# moire_v1_3_rt.net
KiCad netlist of a schematic drawn in EAGLE
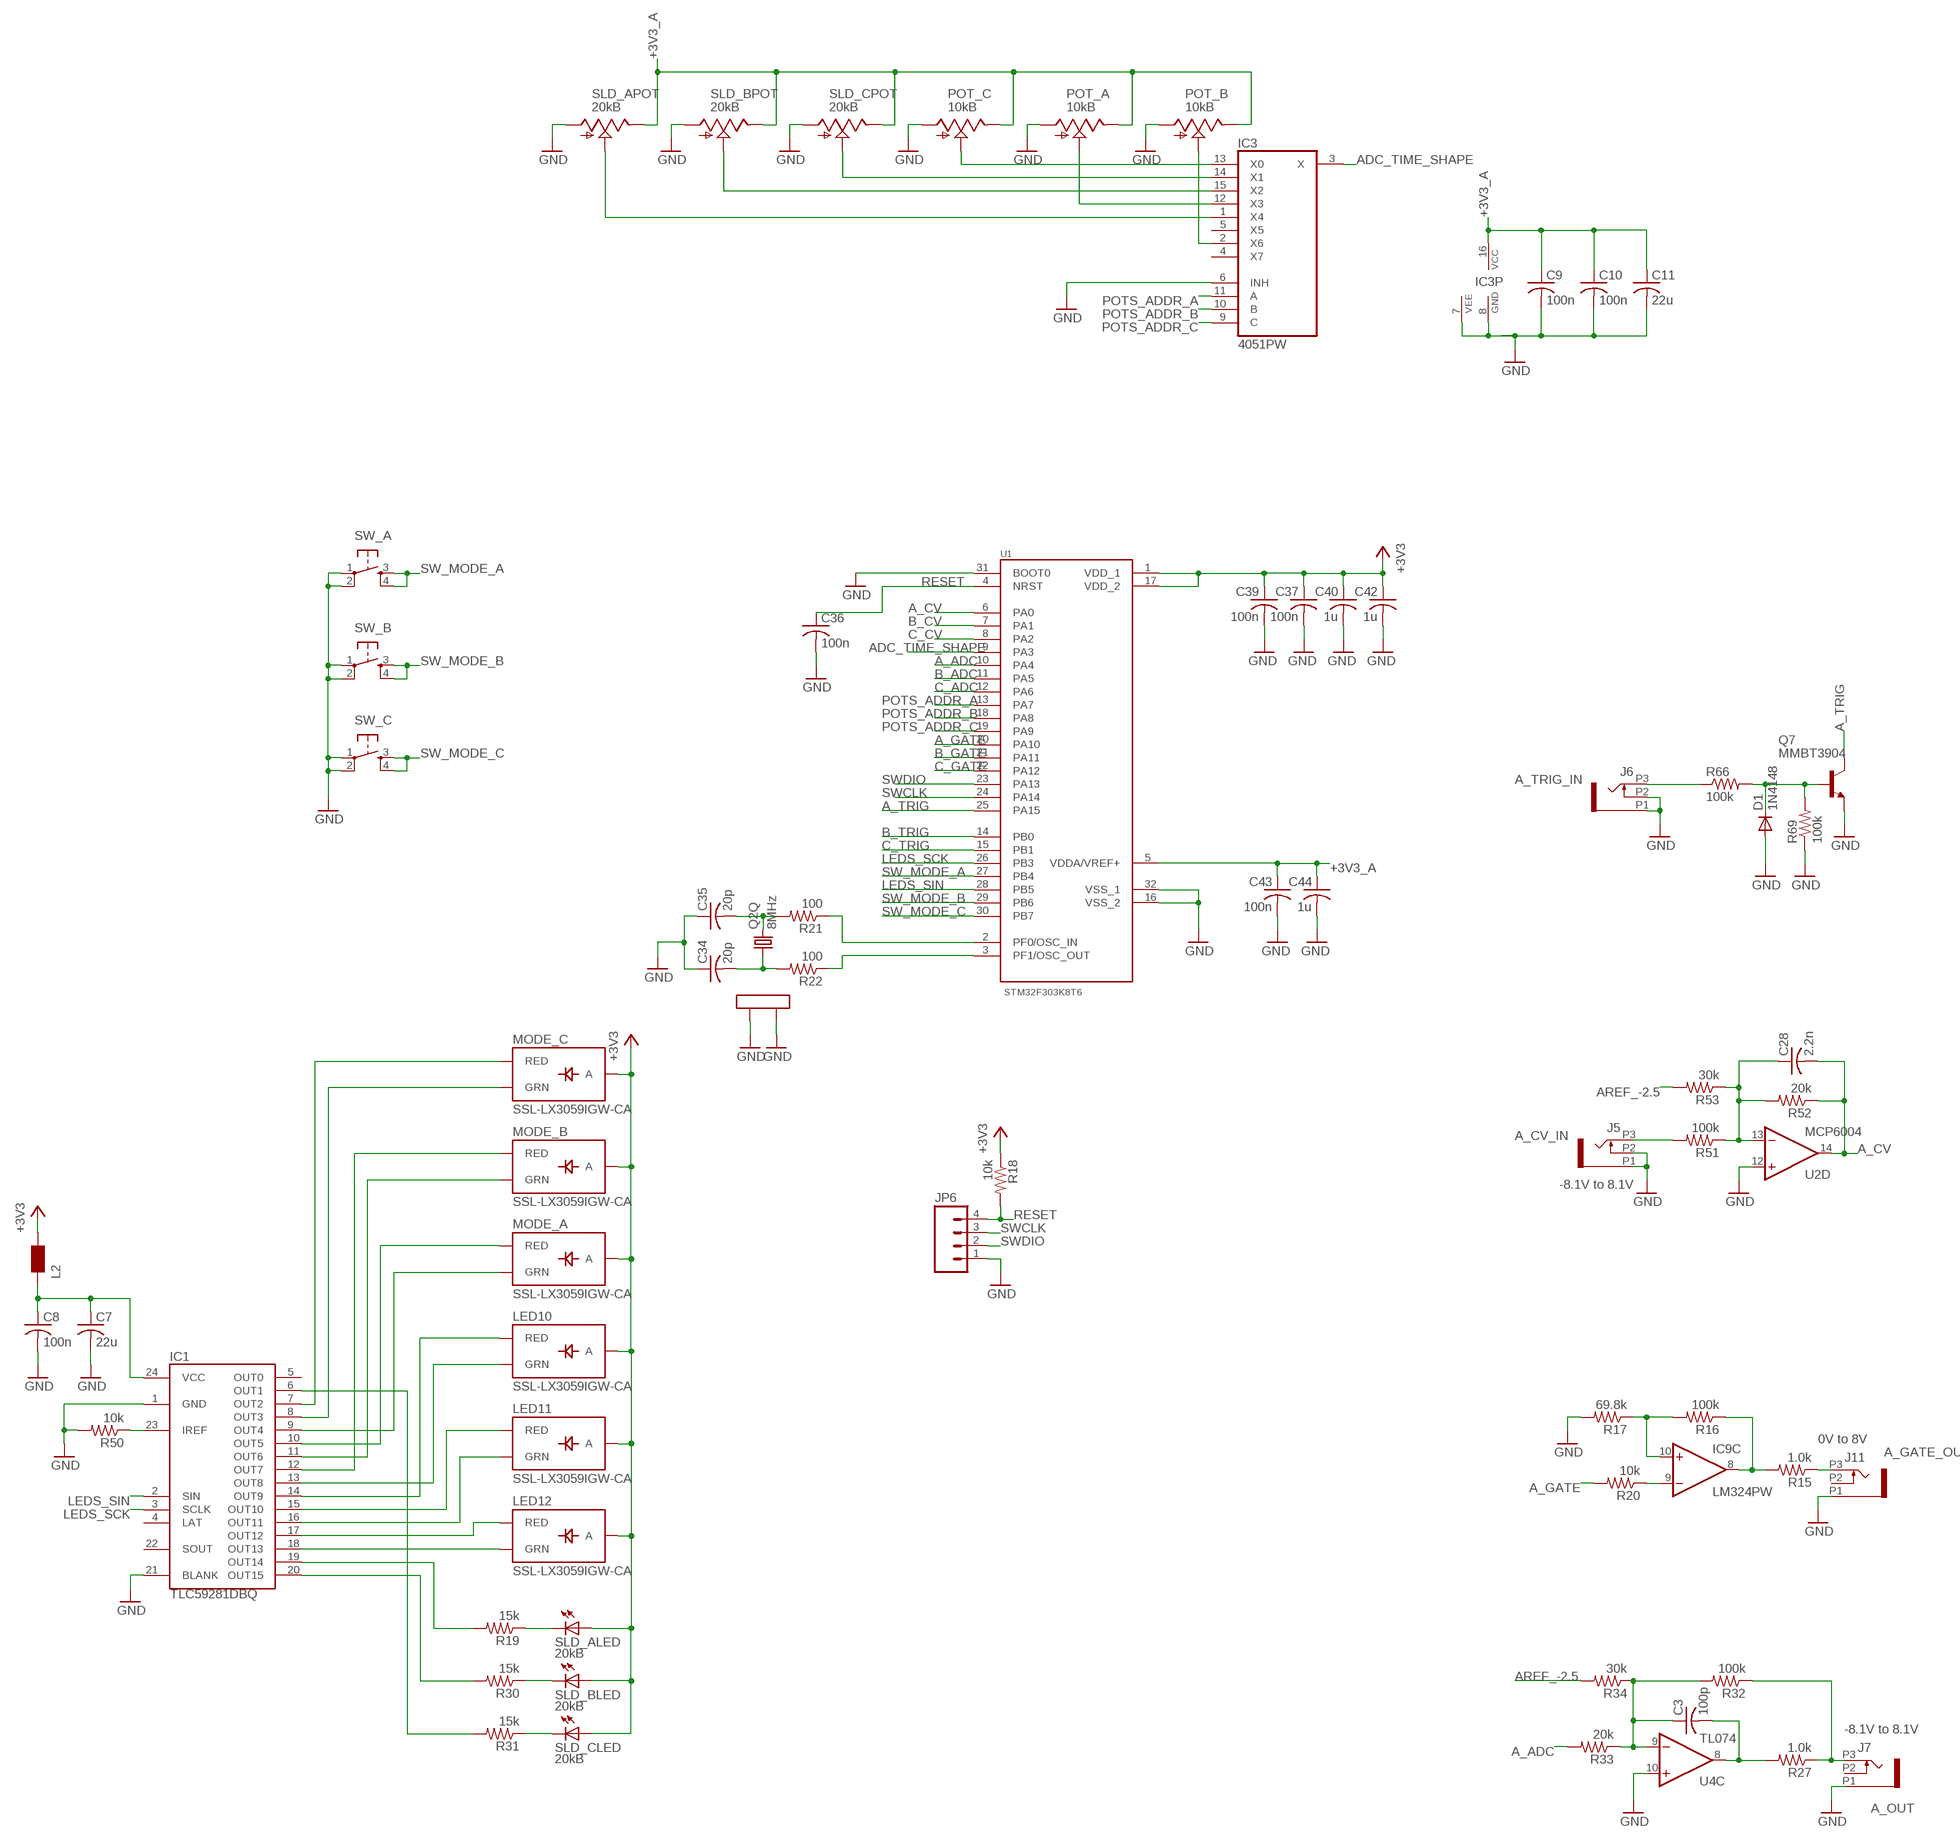
[diagram p0: schematic, sheet 1, part 1 of 2]
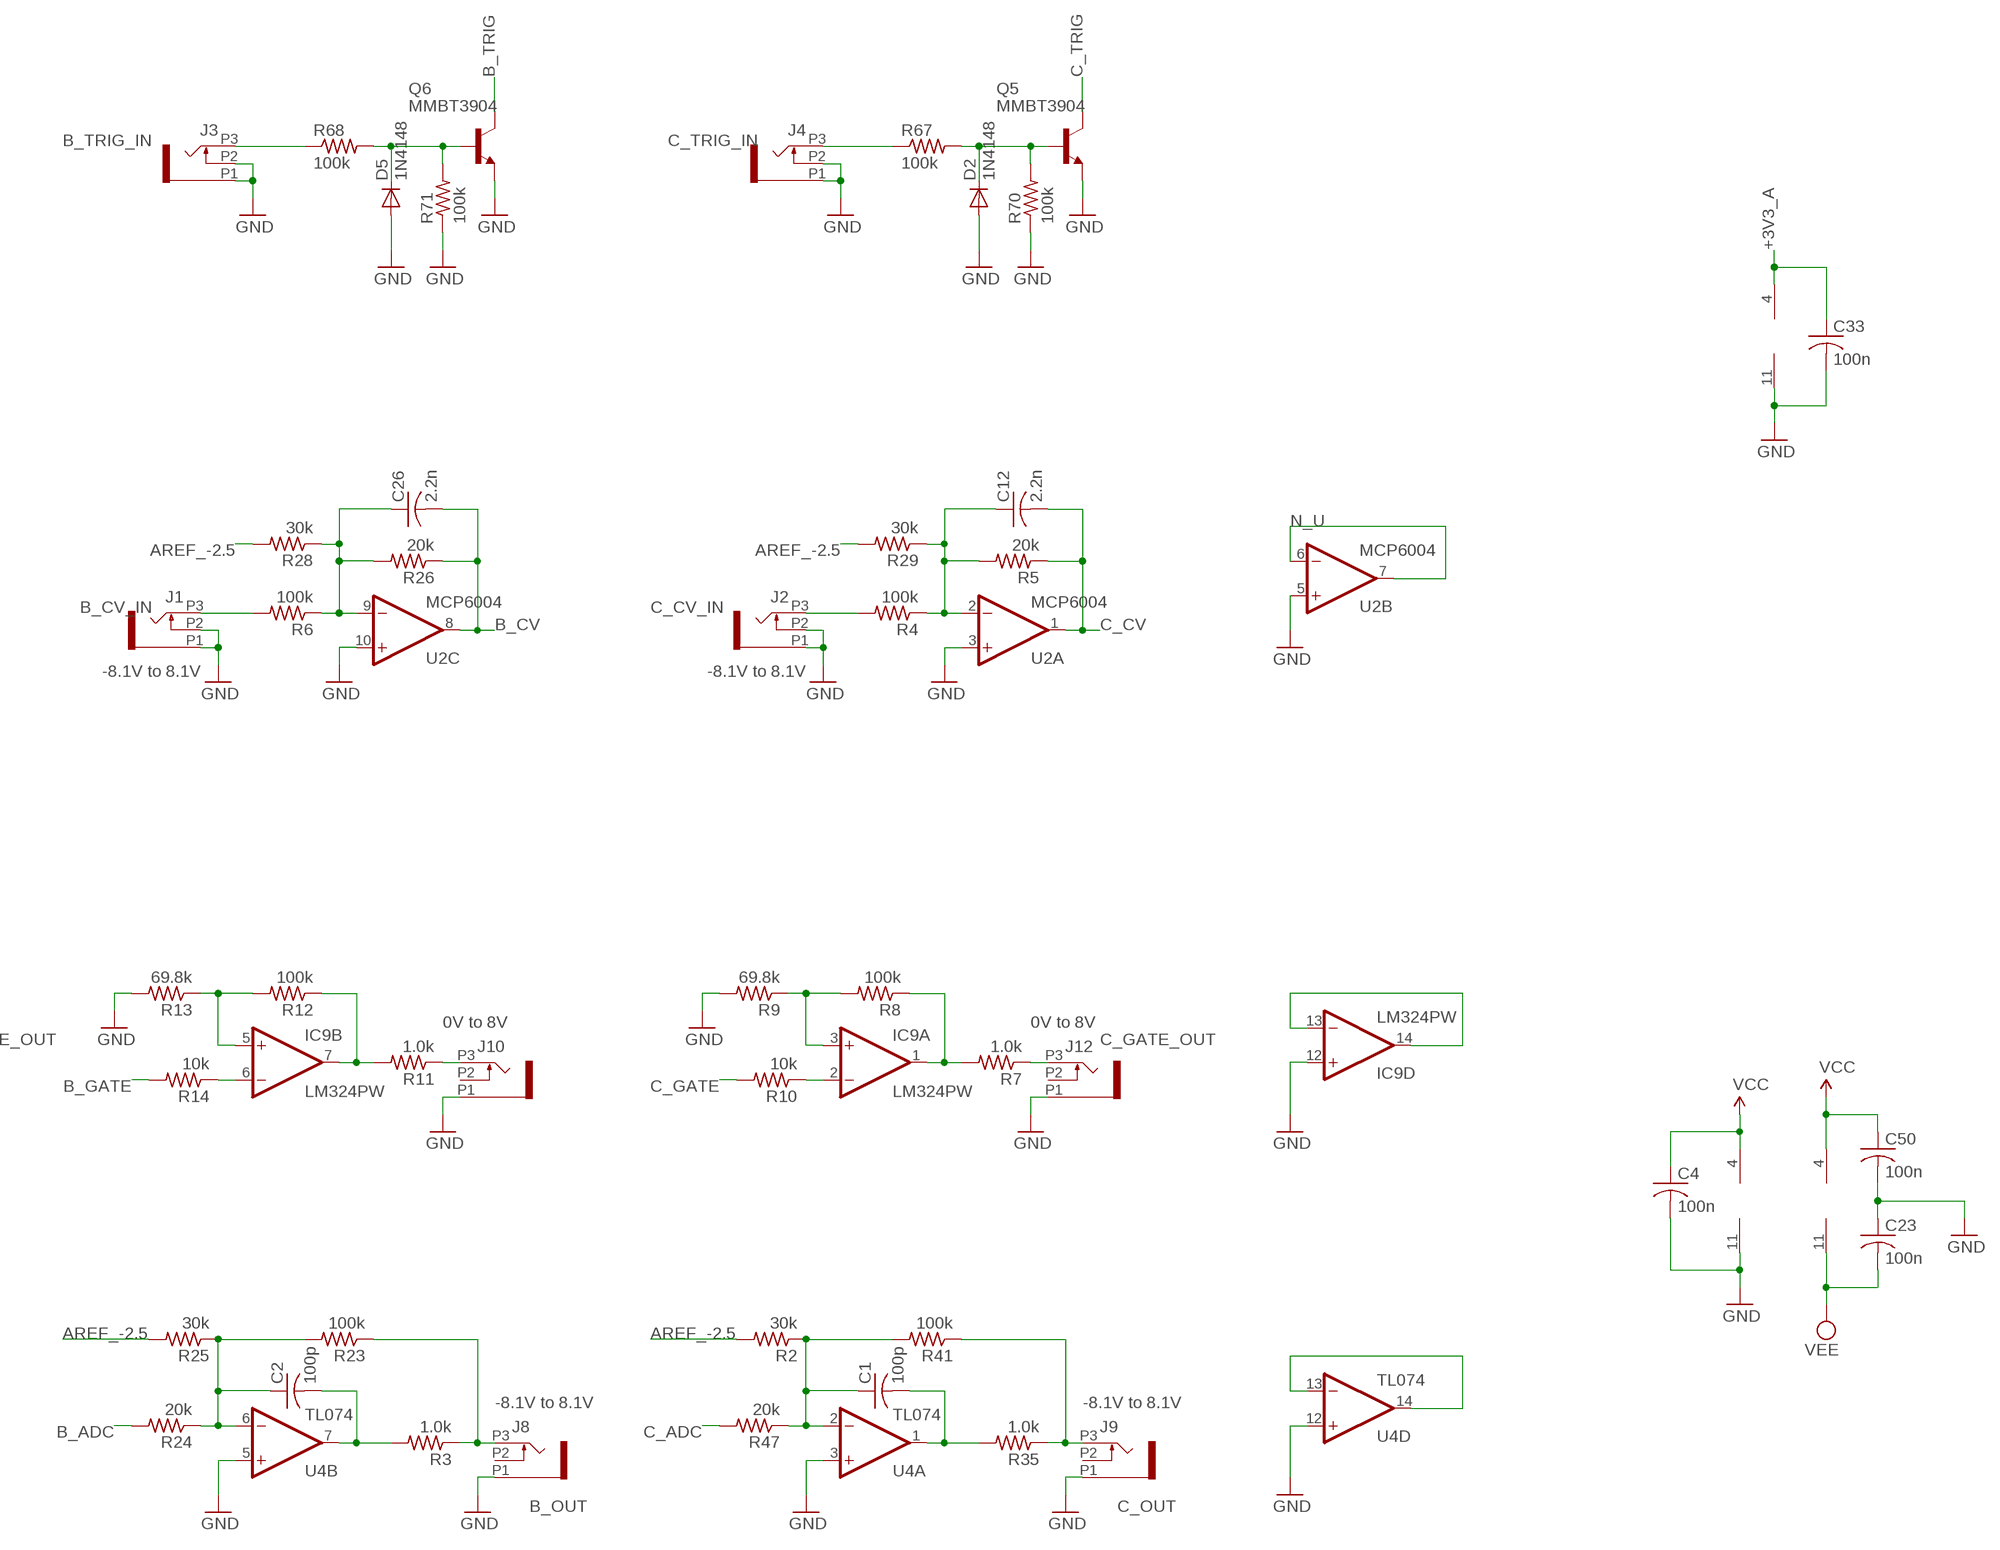
[diagram p1: schematic, sheet 1, part 2 of 2]
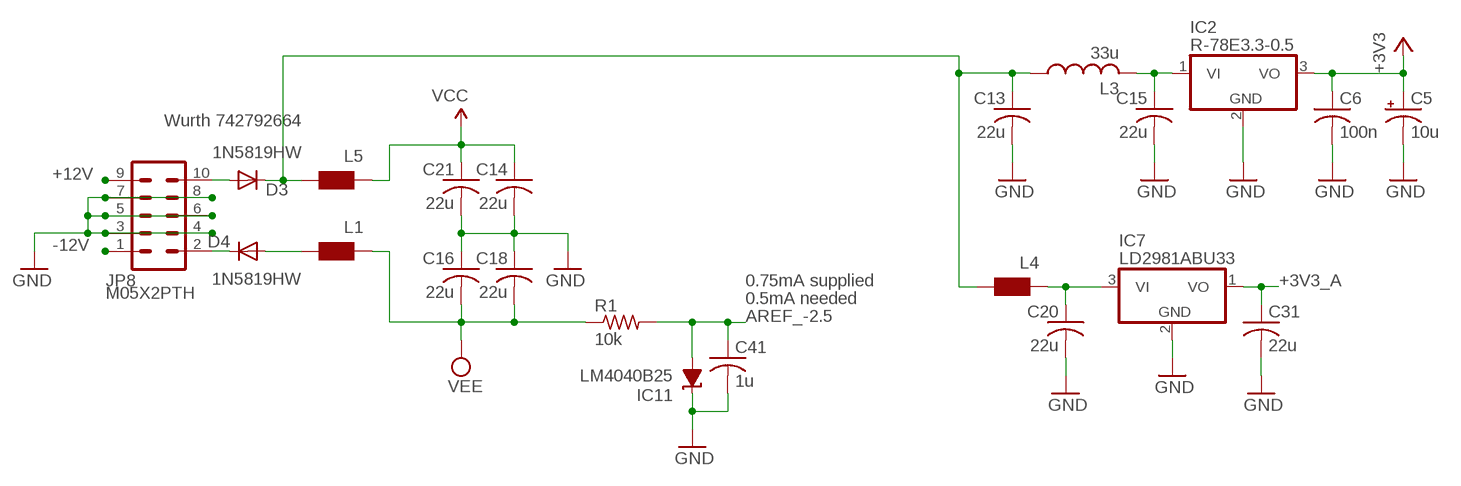
[diagram p2: schematic, sheet 2]

(export (version "E")
  (design (tool "Eeschema 10.0.6"))
  (components
    (comp (ref "C5")
      (value "10u")
      (footprint "eagle-import:PANASONIC_A")
      (libsource (lib "eagle-import") (part "CPOL-USA"))
    )
    (comp (ref "C6")
      (value "100n")
      (footprint "eagle-import:C0603")
      (libsource (lib "eagle-import") (part "C-USC0603"))
    )
    (comp (ref "C13")
      (value "22u")
      (footprint "eagle-import:C1206")
      (libsource (lib "eagle-import") (part "C-USC1206"))
    )
    (comp (ref "C14")
      (value "22u")
      (footprint "eagle-import:C1206")
      (libsource (lib "eagle-import") (part "C-USC1206"))
    )
    (comp (ref "C15")
      (value "22u")
      (footprint "eagle-import:C1206")
      (libsource (lib "eagle-import") (part "C-USC1206"))
    )
    (comp (ref "C16")
      (value "22u")
      (footprint "eagle-import:C1206")
      (libsource (lib "eagle-import") (part "C-USC1206"))
    )
    (comp (ref "C18")
      (value "22u")
      (footprint "eagle-import:C1206")
      (libsource (lib "eagle-import") (part "C-USC1206"))
    )
    (comp (ref "C20")
      (value "22u")
      (footprint "eagle-import:C1206")
      (libsource (lib "eagle-import") (part "C-USC1206"))
    )
    (comp (ref "C21")
      (value "22u")
      (footprint "eagle-import:C1206")
      (libsource (lib "eagle-import") (part "C-USC1206"))
    )
    (comp (ref "C31")
      (value "22u")
      (footprint "eagle-import:C1206")
      (libsource (lib "eagle-import") (part "C-USC1206"))
    )
    (comp (ref "C41")
      (value "1u")
      (footprint "eagle-import:C0603")
      (libsource (lib "eagle-import") (part "C-USC0603"))
    )
    (comp (ref "D3")
      (value "1N5819HW")
      (footprint "eagle-import:SOD123")
      (libsource (lib "eagle-import") (part "DIODE-SOD123"))
    )
    (comp (ref "D4")
      (value "1N5819HW")
      (footprint "eagle-import:SOD123")
      (libsource (lib "eagle-import") (part "DIODE-SOD123"))
    )
    (comp (ref "IC2")
      (value "R-78E3.3-0.5")
      (footprint "eagle-import:WE78")
      (libsource (lib "eagle-import") (part "WE173950378"))
    )
    (comp (ref "IC7")
      (value "LD2981ABU33")
      (footprint "eagle-import:SOT89")
      (libsource (lib "eagle-import") (part "LD2981ABU"))
    )
    (comp (ref "IC11")
      (value "LM4040B25")
      (footprint "eagle-import:DBZ_R-PDSO-G3")
      (libsource (lib "eagle-import") (part "LM4041DBZB12"))
    )
    (comp (ref "JP8")
      (value "M05X2PTH")
      (footprint "eagle-import:2X5-PTH")
      (libsource (lib "eagle-import") (part "M05X2PTH"))
    )
    (comp (ref "L1")
      (value "WE-CBF_0603")
      (footprint "eagle-import:0603")
      (libsource (lib "eagle-import") (part "WE-CBF_0603"))
    )
    (comp (ref "L3")
      (value "33u")
      (footprint "eagle-import:L2012C")
      (libsource (lib "eagle-import") (part "L-USL2012C"))
    )
    (comp (ref "L4")
      (value "WE-CBF_0603")
      (footprint "eagle-import:0603")
      (libsource (lib "eagle-import") (part "WE-CBF_0603"))
    )
    (comp (ref "L5")
      (value "WE-CBF_0603")
      (footprint "eagle-import:0603")
      (libsource (lib "eagle-import") (part "WE-CBF_0603"))
    )
    (comp (ref "R1")
      (value "10k")
      (footprint "eagle-import:R0603")
      (libsource (lib "eagle-import") (part "R-US_R0603"))
    )
    (comp (ref "C1")
      (value "100p")
      (footprint "eagle-import:C0603")
      (libsource (lib "eagle-import") (part "C-USC0603"))
    )
    (comp (ref "C2")
      (value "100p")
      (footprint "eagle-import:C0603")
      (libsource (lib "eagle-import") (part "C-USC0603"))
    )
    (comp (ref "C3")
      (value "100p")
      (footprint "eagle-import:C0603")
      (libsource (lib "eagle-import") (part "C-USC0603"))
    )
    (comp (ref "C4")
      (value "100n")
      (footprint "eagle-import:C0603")
      (libsource (lib "eagle-import") (part "C-USC0603"))
    )
    (comp (ref "C7")
      (value "22u")
      (footprint "eagle-import:C1206")
      (libsource (lib "eagle-import") (part "C-USC1206"))
    )
    (comp (ref "C8")
      (value "100n")
      (footprint "eagle-import:C0603")
      (libsource (lib "eagle-import") (part "C-USC0603"))
    )
    (comp (ref "C9")
      (value "100n")
      (footprint "eagle-import:C0603")
      (libsource (lib "eagle-import") (part "C-USC0603"))
    )
    (comp (ref "C10")
      (value "100n")
      (footprint "eagle-import:C0603")
      (libsource (lib "eagle-import") (part "C-USC0603"))
    )
    (comp (ref "C11")
      (value "22u")
      (footprint "eagle-import:C1206")
      (libsource (lib "eagle-import") (part "C-USC1206"))
    )
    (comp (ref "C12")
      (value "2.2n")
      (footprint "eagle-import:C0603")
      (libsource (lib "eagle-import") (part "C-USC0603"))
    )
    (comp (ref "C23")
      (value "100n")
      (footprint "eagle-import:C0603")
      (libsource (lib "eagle-import") (part "C-USC0603"))
    )
    (comp (ref "C26")
      (value "2.2n")
      (footprint "eagle-import:C0603")
      (libsource (lib "eagle-import") (part "C-USC0603"))
    )
    (comp (ref "C28")
      (value "2.2n")
      (footprint "eagle-import:C0603")
      (libsource (lib "eagle-import") (part "C-USC0603"))
    )
    (comp (ref "C33")
      (value "100n")
      (footprint "eagle-import:C0603")
      (libsource (lib "eagle-import") (part "C-USC0603"))
    )
    (comp (ref "C34")
      (value "20p")
      (footprint "eagle-import:C0603")
      (libsource (lib "eagle-import") (part "C-USC0603"))
    )
    (comp (ref "C35")
      (value "20p")
      (footprint "eagle-import:C0603")
      (libsource (lib "eagle-import") (part "C-USC0603"))
    )
    (comp (ref "C36")
      (value "100n")
      (footprint "eagle-import:C0603")
      (libsource (lib "eagle-import") (part "C-USC0603"))
    )
    (comp (ref "C37")
      (value "100n")
      (footprint "eagle-import:C0603")
      (libsource (lib "eagle-import") (part "C-USC0603"))
    )
    (comp (ref "C39")
      (value "100n")
      (footprint "eagle-import:C0603")
      (libsource (lib "eagle-import") (part "C-USC0603"))
    )
    (comp (ref "C40")
      (value "1u")
      (footprint "eagle-import:C0603")
      (libsource (lib "eagle-import") (part "C-USC0603"))
    )
    (comp (ref "C42")
      (value "1u")
      (footprint "eagle-import:C0603")
      (libsource (lib "eagle-import") (part "C-USC0603"))
    )
    (comp (ref "C43")
      (value "100n")
      (footprint "eagle-import:C0603")
      (libsource (lib "eagle-import") (part "C-USC0603"))
    )
    (comp (ref "C44")
      (value "1u")
      (footprint "eagle-import:C0603")
      (libsource (lib "eagle-import") (part "C-USC0603"))
    )
    (comp (ref "C50")
      (value "100n")
      (footprint "eagle-import:C0603")
      (libsource (lib "eagle-import") (part "C-USC0603"))
    )
    (comp (ref "D1")
      (value "1N4148")
      (footprint "eagle-import:SOD523")
      (libsource (lib "eagle-import") (part "DIODE-SOD523"))
    )
    (comp (ref "D2")
      (value "1N4148")
      (footprint "eagle-import:SOD523")
      (libsource (lib "eagle-import") (part "DIODE-SOD523"))
    )
    (comp (ref "D5")
      (value "1N4148")
      (footprint "eagle-import:SOD523")
      (libsource (lib "eagle-import") (part "DIODE-SOD523"))
    )
    (comp (ref "IC1")
      (value "TLC59281DBQ")
      (footprint "eagle-import:TSSOP24_0635")
      (libsource (lib "eagle-import") (part "TLC59281DBQ"))
    )
    (comp (ref "IC3")
      (value "4051PW")
      (footprint "eagle-import:TSSOP16_065")
      (libsource (lib "eagle-import") (part "4051PW"))
    )
    (comp (ref "IC9")
      (value "LM324PW")
      (footprint "eagle-import:TSSOP14_065")
      (libsource (lib "eagle-import") (part "TL074PW"))
    )
    (comp (ref "J1")
      (value "PJ301_THONKICONN6")
      (footprint "eagle-import:WQP_PJ_301M6")
      (libsource (lib "eagle-import") (part "PJ301_THONKICONN6"))
    )
    (comp (ref "J2")
      (value "PJ301_THONKICONN6")
      (footprint "eagle-import:WQP_PJ_301M6")
      (libsource (lib "eagle-import") (part "PJ301_THONKICONN6"))
    )
    (comp (ref "J3")
      (value "PJ301_THONKICONN6")
      (footprint "eagle-import:WQP_PJ_301M6")
      (libsource (lib "eagle-import") (part "PJ301_THONKICONN6"))
    )
    (comp (ref "J4")
      (value "PJ301_THONKICONN6")
      (footprint "eagle-import:WQP_PJ_301M6")
      (libsource (lib "eagle-import") (part "PJ301_THONKICONN6"))
    )
    (comp (ref "J5")
      (value "PJ301_THONKICONN6")
      (footprint "eagle-import:WQP_PJ_301M6")
      (libsource (lib "eagle-import") (part "PJ301_THONKICONN6"))
    )
    (comp (ref "J6")
      (value "PJ301_THONKICONN6")
      (footprint "eagle-import:WQP_PJ_301M6")
      (libsource (lib "eagle-import") (part "PJ301_THONKICONN6"))
    )
    (comp (ref "J7")
      (value "PJ301_THONKICONN6")
      (footprint "eagle-import:WQP_PJ_301M6")
      (libsource (lib "eagle-import") (part "PJ301_THONKICONN6"))
    )
    (comp (ref "J8")
      (value "PJ301_THONKICONN6")
      (footprint "eagle-import:WQP_PJ_301M6")
      (libsource (lib "eagle-import") (part "PJ301_THONKICONN6"))
    )
    (comp (ref "J9")
      (value "PJ301_THONKICONN6")
      (footprint "eagle-import:WQP_PJ_301M6")
      (libsource (lib "eagle-import") (part "PJ301_THONKICONN6"))
    )
    (comp (ref "J10")
      (value "PJ301_THONKICONN6")
      (footprint "eagle-import:WQP_PJ_301M6")
      (libsource (lib "eagle-import") (part "PJ301_THONKICONN6"))
    )
    (comp (ref "J11")
      (value "PJ301_THONKICONN6")
      (footprint "eagle-import:WQP_PJ_301M6")
      (libsource (lib "eagle-import") (part "PJ301_THONKICONN6"))
    )
    (comp (ref "J12")
      (value "PJ301_THONKICONN6")
      (footprint "eagle-import:WQP_PJ_301M6")
      (libsource (lib "eagle-import") (part "PJ301_THONKICONN6"))
    )
    (comp (ref "JP6")
      (value "M04PTH")
      (footprint "eagle-import:1X04")
      (libsource (lib "eagle-import") (part "M04PTH"))
    )
    (comp (ref "L2")
      (value "WE-CBF_0603")
      (footprint "eagle-import:0603")
      (libsource (lib "eagle-import") (part "WE-CBF_0603"))
    )
    (comp (ref "LED10")
      (value "SSL-LX3059IGW-CA")
      (footprint "eagle-import:LED-BICOLOR-THROUGHHOLE-LUMEX")
      (libsource (lib "eagle-import") (part "LED-BICOLOR-THROUGHHOLE-CA"))
    )
    (comp (ref "LED11")
      (value "SSL-LX3059IGW-CA")
      (footprint "eagle-import:LED-BICOLOR-THROUGHHOLE-LUMEX")
      (libsource (lib "eagle-import") (part "LED-BICOLOR-THROUGHHOLE-CA"))
    )
    (comp (ref "LED12")
      (value "SSL-LX3059IGW-CA")
      (footprint "eagle-import:LED-BICOLOR-THROUGHHOLE-LUMEX")
      (libsource (lib "eagle-import") (part "LED-BICOLOR-THROUGHHOLE-CA"))
    )
    (comp (ref "MODE_A")
      (value "SSL-LX3059IGW-CA")
      (footprint "eagle-import:LED-BICOLOR-THROUGHHOLE-LUMEX")
      (libsource (lib "eagle-import") (part "LED-BICOLOR-THROUGHHOLE-CA"))
    )
    (comp (ref "MODE_B")
      (value "SSL-LX3059IGW-CA")
      (footprint "eagle-import:LED-BICOLOR-THROUGHHOLE-LUMEX")
      (libsource (lib "eagle-import") (part "LED-BICOLOR-THROUGHHOLE-CA"))
    )
    (comp (ref "MODE_C")
      (value "SSL-LX3059IGW-CA")
      (footprint "eagle-import:LED-BICOLOR-THROUGHHOLE-LUMEX")
      (libsource (lib "eagle-import") (part "LED-BICOLOR-THROUGHHOLE-CA"))
    )
    (comp (ref "POT_A")
      (value "10kB")
      (footprint "eagle-import:ALPS_POT_VERTICAL")
      (libsource (lib "eagle-import") (part "POT_USVERTICAL"))
    )
    (comp (ref "POT_B")
      (value "10kB")
      (footprint "eagle-import:ALPS_POT_VERTICAL")
      (libsource (lib "eagle-import") (part "POT_USVERTICAL"))
    )
    (comp (ref "POT_C")
      (value "10kB")
      (footprint "eagle-import:ALPS_POT_VERTICAL")
      (libsource (lib "eagle-import") (part "POT_USVERTICAL"))
    )
    (comp (ref "Q2")
      (value "8MHz")
      (footprint "eagle-import:CTS406")
      (libsource (lib "eagle-import") (part "CRYSTAL"))
    )
    (comp (ref "Q5")
      (value "MMBT3904")
      (footprint "eagle-import:SOT23-BEC")
      (libsource (lib "eagle-import") (part "-NPN-SOT23-BECMMBT3904LT1"))
    )
    (comp (ref "Q6")
      (value "MMBT3904")
      (footprint "eagle-import:SOT23-BEC")
      (libsource (lib "eagle-import") (part "-NPN-SOT23-BECMMBT3904LT1"))
    )
    (comp (ref "Q7")
      (value "MMBT3904")
      (footprint "eagle-import:SOT23-BEC")
      (libsource (lib "eagle-import") (part "-NPN-SOT23-BECMMBT3904LT1"))
    )
    (comp (ref "R2")
      (value "30k")
      (footprint "eagle-import:R0603")
      (libsource (lib "eagle-import") (part "R-US_R0603"))
    )
    (comp (ref "R3")
      (value "1.0k")
      (footprint "eagle-import:R0603")
      (libsource (lib "eagle-import") (part "R-US_R0603"))
    )
    (comp (ref "R4")
      (value "100k")
      (footprint "eagle-import:R0603")
      (libsource (lib "eagle-import") (part "R-US_R0603"))
    )
    (comp (ref "R5")
      (value "20k")
      (footprint "eagle-import:R0603")
      (libsource (lib "eagle-import") (part "R-US_R0603"))
    )
    (comp (ref "R6")
      (value "100k")
      (footprint "eagle-import:R0603")
      (libsource (lib "eagle-import") (part "R-US_R0603"))
    )
    (comp (ref "R7")
      (value "1.0k")
      (footprint "eagle-import:R0603")
      (libsource (lib "eagle-import") (part "R-US_R0603"))
    )
    (comp (ref "R8")
      (value "100k")
      (footprint "eagle-import:R0603")
      (libsource (lib "eagle-import") (part "R-US_R0603"))
    )
    (comp (ref "R9")
      (value "69.8k")
      (footprint "eagle-import:R0603")
      (libsource (lib "eagle-import") (part "R-US_R0603"))
    )
    (comp (ref "R10")
      (value "10k")
      (footprint "eagle-import:R0603")
      (libsource (lib "eagle-import") (part "R-US_R0603"))
    )
    (comp (ref "R11")
      (value "1.0k")
      (footprint "eagle-import:R0603")
      (libsource (lib "eagle-import") (part "R-US_R0603"))
    )
    (comp (ref "R12")
      (value "100k")
      (footprint "eagle-import:R0603")
      (libsource (lib "eagle-import") (part "R-US_R0603"))
    )
    (comp (ref "R13")
      (value "69.8k")
      (footprint "eagle-import:R0603")
      (libsource (lib "eagle-import") (part "R-US_R0603"))
    )
    (comp (ref "R14")
      (value "10k")
      (footprint "eagle-import:R0603")
      (libsource (lib "eagle-import") (part "R-US_R0603"))
    )
    (comp (ref "R15")
      (value "1.0k")
      (footprint "eagle-import:R0603")
      (libsource (lib "eagle-import") (part "R-US_R0603"))
    )
    (comp (ref "R16")
      (value "100k")
      (footprint "eagle-import:R0603")
      (libsource (lib "eagle-import") (part "R-US_R0603"))
    )
    (comp (ref "R17")
      (value "69.8k")
      (footprint "eagle-import:R0603")
      (libsource (lib "eagle-import") (part "R-US_R0603"))
    )
    (comp (ref "R18")
      (value "10k")
      (footprint "eagle-import:R0603")
      (libsource (lib "eagle-import") (part "R-US_R0603"))
    )
    (comp (ref "R19")
      (value "15k")
      (footprint "eagle-import:R0603")
      (libsource (lib "eagle-import") (part "R-US_R0603"))
    )
    (comp (ref "R20")
      (value "10k")
      (footprint "eagle-import:R0603")
      (libsource (lib "eagle-import") (part "R-US_R0603"))
    )
    (comp (ref "R21")
      (value "100")
      (footprint "eagle-import:R0603")
      (libsource (lib "eagle-import") (part "R-US_R0603"))
    )
    (comp (ref "R22")
      (value "100")
      (footprint "eagle-import:R0603")
      (libsource (lib "eagle-import") (part "R-US_R0603"))
    )
    (comp (ref "R23")
      (value "100k")
      (footprint "eagle-import:R0603")
      (libsource (lib "eagle-import") (part "R-US_R0603"))
    )
    (comp (ref "R24")
      (value "20k")
      (footprint "eagle-import:R0603")
      (libsource (lib "eagle-import") (part "R-US_R0603"))
    )
    (comp (ref "R25")
      (value "30k")
      (footprint "eagle-import:R0603")
      (libsource (lib "eagle-import") (part "R-US_R0603"))
    )
    (comp (ref "R26")
      (value "20k")
      (footprint "eagle-import:R0603")
      (libsource (lib "eagle-import") (part "R-US_R0603"))
    )
    (comp (ref "R27")
      (value "1.0k")
      (footprint "eagle-import:R0603")
      (libsource (lib "eagle-import") (part "R-US_R0603"))
    )
    (comp (ref "R28")
      (value "30k")
      (footprint "eagle-import:R0603")
      (libsource (lib "eagle-import") (part "R-US_R0603"))
    )
    (comp (ref "R29")
      (value "30k")
      (footprint "eagle-import:R0603")
      (libsource (lib "eagle-import") (part "R-US_R0603"))
    )
    (comp (ref "R30")
      (value "15k")
      (footprint "eagle-import:R0603")
      (libsource (lib "eagle-import") (part "R-US_R0603"))
    )
    (comp (ref "R31")
      (value "15k")
      (footprint "eagle-import:R0603")
      (libsource (lib "eagle-import") (part "R-US_R0603"))
    )
    (comp (ref "R32")
      (value "100k")
      (footprint "eagle-import:R0603")
      (libsource (lib "eagle-import") (part "R-US_R0603"))
    )
    (comp (ref "R33")
      (value "20k")
      (footprint "eagle-import:R0603")
      (libsource (lib "eagle-import") (part "R-US_R0603"))
    )
    (comp (ref "R34")
      (value "30k")
      (footprint "eagle-import:R0603")
      (libsource (lib "eagle-import") (part "R-US_R0603"))
    )
    (comp (ref "R35")
      (value "1.0k")
      (footprint "eagle-import:R0603")
      (libsource (lib "eagle-import") (part "R-US_R0603"))
    )
    (comp (ref "R41")
      (value "100k")
      (footprint "eagle-import:R0603")
      (libsource (lib "eagle-import") (part "R-US_R0603"))
    )
    (comp (ref "R47")
      (value "20k")
      (footprint "eagle-import:R0603")
      (libsource (lib "eagle-import") (part "R-US_R0603"))
    )
    (comp (ref "R50")
      (value "10k")
      (footprint "eagle-import:R0603")
      (libsource (lib "eagle-import") (part "R-US_R0603"))
    )
    (comp (ref "R51")
      (value "100k")
      (footprint "eagle-import:R0603")
      (libsource (lib "eagle-import") (part "R-US_R0603"))
    )
    (comp (ref "R52")
      (value "20k")
      (footprint "eagle-import:R0603")
      (libsource (lib "eagle-import") (part "R-US_R0603"))
    )
    (comp (ref "R53")
      (value "30k")
      (footprint "eagle-import:R0603")
      (libsource (lib "eagle-import") (part "R-US_R0603"))
    )
    (comp (ref "R66")
      (value "100k")
      (footprint "eagle-import:R0603")
      (libsource (lib "eagle-import") (part "R-US_R0603"))
    )
    (comp (ref "R67")
      (value "100k")
      (footprint "eagle-import:R0603")
      (libsource (lib "eagle-import") (part "R-US_R0603"))
    )
    (comp (ref "R68")
      (value "100k")
      (footprint "eagle-import:R0603")
      (libsource (lib "eagle-import") (part "R-US_R0603"))
    )
    (comp (ref "R69")
      (value "100k")
      (footprint "eagle-import:R0603")
      (libsource (lib "eagle-import") (part "R-US_R0603"))
    )
    (comp (ref "R70")
      (value "100k")
      (footprint "eagle-import:R0603")
      (libsource (lib "eagle-import") (part "R-US_R0603"))
    )
    (comp (ref "R71")
      (value "100k")
      (footprint "eagle-import:R0603")
      (libsource (lib "eagle-import") (part "R-US_R0603"))
    )
    (comp (ref "SLD_A")
      (value "20kB")
      (footprint "eagle-import:BOURNS_SLIDER")
      (libsource (lib "eagle-import") (part "BOURNS_SLIDER"))
    )
    (comp (ref "SLD_B")
      (value "20kB")
      (footprint "eagle-import:BOURNS_SLIDER")
      (libsource (lib "eagle-import") (part "BOURNS_SLIDER"))
    )
    (comp (ref "SLD_C")
      (value "20kB")
      (footprint "eagle-import:BOURNS_SLIDER")
      (libsource (lib "eagle-import") (part "BOURNS_SLIDER"))
    )
    (comp (ref "SW_A")
      (value "TAC_SWITCHPTH")
      (footprint "eagle-import:TACTILE-PTH")
      (libsource (lib "eagle-import") (part "TAC_SWITCHPTH"))
    )
    (comp (ref "SW_B")
      (value "TAC_SWITCHPTH")
      (footprint "eagle-import:TACTILE-PTH")
      (libsource (lib "eagle-import") (part "TAC_SWITCHPTH"))
    )
    (comp (ref "SW_C")
      (value "TAC_SWITCHPTH")
      (footprint "eagle-import:TACTILE-PTH")
      (libsource (lib "eagle-import") (part "TAC_SWITCHPTH"))
    )
    (comp (ref "U1")
      (value "STM32F303K8T6")
      (footprint "eagle-import:QFP80P900X900X160-32N")
      (fields (field (name "MF") "STMicroelectronics"))
      (libsource (lib "eagle-import") (part "STM32F303K8T6"))
    )
    (comp (ref "U2")
      (value "MCP6004")
      (footprint "eagle-import:SO14")
      (libsource (lib "eagle-import") (part "MCP6004_SMD"))
    )
    (comp (ref "U4")
      (value "TL074")
      (footprint "eagle-import:SO14")
      (libsource (lib "eagle-import") (part "TL074_SMD"))
    )
  )
  (nets
    (net (code "1") (name "+3V3") (class "Default")
      (node (ref "C37") (pin "1") (pinfunction "1_1") (pintype "passive"))
      (node (ref "C39") (pin "1") (pinfunction "1_1") (pintype "passive"))
      (node (ref "C40") (pin "1") (pinfunction "1_1") (pintype "passive"))
      (node (ref "C42") (pin "1") (pinfunction "1_1") (pintype "passive"))
      (node (ref "C5") (pin "+") (pinfunction "+_+") (pintype "passive"))
      (node (ref "C6") (pin "1") (pinfunction "1_1") (pintype "passive"))
      (node (ref "IC2") (pin "3") (pinfunction "VO_3") (pintype "passive"))
      (node (ref "L2") (pin "2") (pinfunction "2_2") (pintype "passive"))
      (node (ref "LED10") (pin "A") (pinfunction "A_A") (pintype "bidirectional"))
      (node (ref "LED11") (pin "A") (pinfunction "A_A") (pintype "bidirectional"))
      (node (ref "LED12") (pin "A") (pinfunction "A_A") (pintype "bidirectional"))
      (node (ref "MODE_A") (pin "A") (pinfunction "A_A") (pintype "bidirectional"))
      (node (ref "MODE_B") (pin "A") (pinfunction "A_A") (pintype "bidirectional"))
      (node (ref "MODE_C") (pin "A") (pinfunction "A_A") (pintype "bidirectional"))
      (node (ref "R18") (pin "1") (pinfunction "1_1") (pintype "passive"))
      (node (ref "SLD_A") (pin "B") (pinfunction "A_B") (pintype "passive"))
      (node (ref "SLD_B") (pin "B") (pinfunction "A_B") (pintype "passive"))
      (node (ref "SLD_C") (pin "B") (pinfunction "A_B") (pintype "passive"))
      (node (ref "U1") (pin "1") (pinfunction "VDD_1_1") (pintype "power_in"))
      (node (ref "U1") (pin "17") (pinfunction "VDD_2_17") (pintype "power_in"))
    )
    (net (code "2") (name "+3V3_A") (class "Default")
      (node (ref "C10") (pin "1") (pinfunction "1_1") (pintype "passive"))
      (node (ref "C11") (pin "1") (pinfunction "1_1") (pintype "passive"))
      (node (ref "C31") (pin "1") (pinfunction "1_1") (pintype "passive"))
      (node (ref "C33") (pin "1") (pinfunction "1_1") (pintype "passive"))
      (node (ref "C43") (pin "1") (pinfunction "1_1") (pintype "passive"))
      (node (ref "C44") (pin "1") (pinfunction "1_1") (pintype "passive"))
      (node (ref "C9") (pin "1") (pinfunction "1_1") (pintype "passive"))
      (node (ref "IC3") (pin "16") (pinfunction "VCC_16") (pintype "power_in"))
      (node (ref "IC7") (pin "1") (pinfunction "VO_1") (pintype "passive"))
      (node (ref "POT_A") (pin "P$1") (pinfunction "E_P$1") (pintype "passive"))
      (node (ref "POT_B") (pin "P$1") (pinfunction "E_P$1") (pintype "passive"))
      (node (ref "POT_C") (pin "P$1") (pinfunction "E_P$1") (pintype "passive"))
      (node (ref "SLD_A") (pin "3") (pinfunction "E_3") (pintype "passive"))
      (node (ref "SLD_B") (pin "3") (pinfunction "E_3") (pintype "passive"))
      (node (ref "SLD_C") (pin "3") (pinfunction "E_3") (pintype "passive"))
      (node (ref "U1") (pin "5") (pinfunction "VDDA/VREF+_5") (pintype "power_in"))
      (node (ref "U2") (pin "4") (pinfunction "V+_4") (pintype "power_in"))
    )
    (net (code "3") (name "+12V") (class "Default")
      (node (ref "D3") (pin "A") (pinfunction "A_A") (pintype "passive"))
      (node (ref "JP8") (pin "10") (pinfunction "10_10") (pintype "passive"))
      (node (ref "JP8") (pin "9") (pinfunction "9_9") (pintype "passive"))
    )
    (net (code "4") (name "-12V") (class "Default")
      (node (ref "D4") (pin "C") (pinfunction "C_C") (pintype "passive"))
      (node (ref "JP8") (pin "1") (pinfunction "1_1") (pintype "passive"))
      (node (ref "JP8") (pin "2") (pinfunction "2_2") (pintype "passive"))
    )
    (net (code "5") (name "ADC_TIME_SHAPE") (class "Default")
      (node (ref "IC3") (pin "3") (pinfunction "X_3") (pintype "bidirectional"))
      (node (ref "U1") (pin "9") (pinfunction "PA3_9") (pintype "bidirectional"))
    )
    (net (code "6") (name "AREF_-2.5") (class "Default")
      (node (ref "C41") (pin "1") (pinfunction "1_1") (pintype "passive"))
      (node (ref "IC11") (pin "2") (pinfunction "A_2") (pintype "passive"))
      (node (ref "R1") (pin "2") (pinfunction "2_2") (pintype "passive"))
      (node (ref "R2") (pin "2") (pinfunction "2_2") (pintype "passive"))
      (node (ref "R25") (pin "2") (pinfunction "2_2") (pintype "passive"))
      (node (ref "R28") (pin "2") (pinfunction "2_2") (pintype "passive"))
      (node (ref "R29") (pin "2") (pinfunction "2_2") (pintype "passive"))
      (node (ref "R34") (pin "2") (pinfunction "2_2") (pintype "passive"))
      (node (ref "R53") (pin "2") (pinfunction "2_2") (pintype "passive"))
    )
    (net (code "7") (name "A_ADC") (class "Default")
      (node (ref "R33") (pin "2") (pinfunction "2_2") (pintype "passive"))
      (node (ref "U1") (pin "10") (pinfunction "PA4_10") (pintype "bidirectional"))
    )
    (net (code "8") (name "A_CV") (class "Default")
      (node (ref "C28") (pin "2") (pinfunction "2_2") (pintype "passive"))
      (node (ref "R52") (pin "1") (pinfunction "1_1") (pintype "passive"))
      (node (ref "U1") (pin "6") (pinfunction "PA0_6") (pintype "bidirectional"))
      (node (ref "U2") (pin "14") (pinfunction "OUT_14") (pintype "output"))
    )
    (net (code "9") (name "A_CV_IN") (class "Default")
      (node (ref "J5") (pin "P3") (pinfunction "3_P3") (pintype "passive"))
      (node (ref "R51") (pin "2") (pinfunction "2_2") (pintype "passive"))
    )
    (net (code "10") (name "A_GATE") (class "Default")
      (node (ref "R20") (pin "2") (pinfunction "2_2") (pintype "passive"))
      (node (ref "U1") (pin "20") (pinfunction "PA10_20") (pintype "bidirectional"))
    )
    (net (code "11") (name "A_GATE_OUT") (class "Default")
      (node (ref "J11") (pin "P3") (pinfunction "3_P3") (pintype "passive"))
      (node (ref "R15") (pin "1") (pinfunction "1_1") (pintype "passive"))
    )
    (net (code "12") (name "A_OUT") (class "Default")
      (node (ref "J7") (pin "P3") (pinfunction "3_P3") (pintype "passive"))
      (node (ref "R27") (pin "1") (pinfunction "1_1") (pintype "passive"))
      (node (ref "R32") (pin "1") (pinfunction "1_1") (pintype "passive"))
    )
    (net (code "13") (name "A_TRIG") (class "Default")
      (node (ref "Q7") (pin "C") (pinfunction "C_C") (pintype "passive"))
      (node (ref "U1") (pin "25") (pinfunction "PA15_25") (pintype "bidirectional"))
    )
    (net (code "14") (name "A_TRIG_IN") (class "Default")
      (node (ref "J6") (pin "P3") (pinfunction "3_P3") (pintype "passive"))
      (node (ref "R66") (pin "1") (pinfunction "1_1") (pintype "passive"))
    )
    (net (code "15") (name "B_ADC") (class "Default")
      (node (ref "R24") (pin "2") (pinfunction "2_2") (pintype "passive"))
      (node (ref "U1") (pin "11") (pinfunction "PA5_11") (pintype "bidirectional"))
    )
    (net (code "16") (name "B_CV") (class "Default")
      (node (ref "C26") (pin "2") (pinfunction "2_2") (pintype "passive"))
      (node (ref "R26") (pin "1") (pinfunction "1_1") (pintype "passive"))
      (node (ref "U1") (pin "7") (pinfunction "PA1_7") (pintype "bidirectional"))
      (node (ref "U2") (pin "8") (pinfunction "OUT_8") (pintype "output"))
    )
    (net (code "17") (name "B_CV_IN") (class "Default")
      (node (ref "J1") (pin "P3") (pinfunction "3_P3") (pintype "passive"))
      (node (ref "R6") (pin "2") (pinfunction "2_2") (pintype "passive"))
    )
    (net (code "18") (name "B_GATE") (class "Default")
      (node (ref "R14") (pin "2") (pinfunction "2_2") (pintype "passive"))
      (node (ref "U1") (pin "21") (pinfunction "PA11_21") (pintype "bidirectional"))
    )
    (net (code "19") (name "B_OUT") (class "Default")
      (node (ref "J8") (pin "P3") (pinfunction "3_P3") (pintype "passive"))
      (node (ref "R23") (pin "1") (pinfunction "1_1") (pintype "passive"))
      (node (ref "R3") (pin "1") (pinfunction "1_1") (pintype "passive"))
    )
    (net (code "20") (name "B_TRIG") (class "Default")
      (node (ref "Q6") (pin "C") (pinfunction "C_C") (pintype "passive"))
      (node (ref "U1") (pin "14") (pinfunction "PB0_14") (pintype "bidirectional"))
    )
    (net (code "21") (name "B_TRIG_IN") (class "Default")
      (node (ref "J3") (pin "P3") (pinfunction "3_P3") (pintype "passive"))
      (node (ref "R68") (pin "1") (pinfunction "1_1") (pintype "passive"))
    )
    (net (code "22") (name "C_ADC") (class "Default")
      (node (ref "R47") (pin "2") (pinfunction "2_2") (pintype "passive"))
      (node (ref "U1") (pin "12") (pinfunction "PA6_12") (pintype "bidirectional"))
    )
    (net (code "23") (name "C_CV") (class "Default")
      (node (ref "C12") (pin "2") (pinfunction "2_2") (pintype "passive"))
      (node (ref "R5") (pin "1") (pinfunction "1_1") (pintype "passive"))
      (node (ref "U1") (pin "8") (pinfunction "PA2_8") (pintype "bidirectional"))
      (node (ref "U2") (pin "1") (pinfunction "OUT_1") (pintype "output"))
    )
    (net (code "24") (name "C_CV_IN") (class "Default")
      (node (ref "J2") (pin "P3") (pinfunction "3_P3") (pintype "passive"))
      (node (ref "R4") (pin "2") (pinfunction "2_2") (pintype "passive"))
    )
    (net (code "25") (name "C_GATE") (class "Default")
      (node (ref "R10") (pin "2") (pinfunction "2_2") (pintype "passive"))
      (node (ref "U1") (pin "22") (pinfunction "PA12_22") (pintype "bidirectional"))
    )
    (net (code "26") (name "C_GATE_OUT") (class "Default")
      (node (ref "J12") (pin "P3") (pinfunction "3_P3") (pintype "passive"))
      (node (ref "R7") (pin "1") (pinfunction "1_1") (pintype "passive"))
    )
    (net (code "27") (name "C_OUT") (class "Default")
      (node (ref "J9") (pin "P3") (pinfunction "3_P3") (pintype "passive"))
      (node (ref "R35") (pin "1") (pinfunction "1_1") (pintype "passive"))
      (node (ref "R41") (pin "1") (pinfunction "1_1") (pintype "passive"))
    )
    (net (code "28") (name "C_TRIG") (class "Default")
      (node (ref "Q5") (pin "C") (pinfunction "C_C") (pintype "passive"))
      (node (ref "U1") (pin "15") (pinfunction "PB1_15") (pintype "bidirectional"))
    )
    (net (code "29") (name "C_TRIG_IN") (class "Default")
      (node (ref "J4") (pin "P3") (pinfunction "3_P3") (pintype "passive"))
      (node (ref "R67") (pin "1") (pinfunction "1_1") (pintype "passive"))
    )
    (net (code "30") (name "GND") (class "Default")
      (node (ref "C10") (pin "2") (pinfunction "2_2") (pintype "passive"))
      (node (ref "C11") (pin "2") (pinfunction "2_2") (pintype "passive"))
      (node (ref "C13") (pin "2") (pinfunction "2_2") (pintype "passive"))
      (node (ref "C14") (pin "2") (pinfunction "2_2") (pintype "passive"))
      (node (ref "C15") (pin "2") (pinfunction "2_2") (pintype "passive"))
      (node (ref "C16") (pin "1") (pinfunction "1_1") (pintype "passive"))
      (node (ref "C18") (pin "1") (pinfunction "1_1") (pintype "passive"))
      (node (ref "C20") (pin "2") (pinfunction "2_2") (pintype "passive"))
      (node (ref "C21") (pin "2") (pinfunction "2_2") (pintype "passive"))
      (node (ref "C23") (pin "1") (pinfunction "1_1") (pintype "passive"))
      (node (ref "C31") (pin "2") (pinfunction "2_2") (pintype "passive"))
      (node (ref "C33") (pin "2") (pinfunction "2_2") (pintype "passive"))
      (node (ref "C34") (pin "1") (pinfunction "1_1") (pintype "passive"))
      (node (ref "C35") (pin "1") (pinfunction "1_1") (pintype "passive"))
      (node (ref "C36") (pin "2") (pinfunction "2_2") (pintype "passive"))
      (node (ref "C37") (pin "2") (pinfunction "2_2") (pintype "passive"))
      (node (ref "C39") (pin "2") (pinfunction "2_2") (pintype "passive"))
      (node (ref "C4") (pin "2") (pinfunction "2_2") (pintype "passive"))
      (node (ref "C40") (pin "2") (pinfunction "2_2") (pintype "passive"))
      (node (ref "C41") (pin "2") (pinfunction "2_2") (pintype "passive"))
      (node (ref "C42") (pin "2") (pinfunction "2_2") (pintype "passive"))
      (node (ref "C43") (pin "2") (pinfunction "2_2") (pintype "passive"))
      (node (ref "C44") (pin "2") (pinfunction "2_2") (pintype "passive"))
      (node (ref "C5") (pin "-") (pinfunction "-_-") (pintype "passive"))
      (node (ref "C50") (pin "2") (pinfunction "2_2") (pintype "passive"))
      (node (ref "C6") (pin "2") (pinfunction "2_2") (pintype "passive"))
      (node (ref "C7") (pin "2") (pinfunction "2_2") (pintype "passive"))
      (node (ref "C8") (pin "2") (pinfunction "2_2") (pintype "passive"))
      (node (ref "C9") (pin "2") (pinfunction "2_2") (pintype "passive"))
      (node (ref "D1") (pin "A") (pinfunction "A_A") (pintype "passive"))
      (node (ref "D2") (pin "A") (pinfunction "A_A") (pintype "passive"))
      (node (ref "D5") (pin "A") (pinfunction "A_A") (pintype "passive"))
      (node (ref "IC1") (pin "1") (pinfunction "GND_1") (pintype "bidirectional"))
      (node (ref "IC1") (pin "21") (pinfunction "BLANK_21") (pintype "bidirectional"))
      (node (ref "IC11") (pin "1") (pinfunction "C_1") (pintype "passive"))
      (node (ref "IC2") (pin "2") (pinfunction "GND_2") (pintype "passive"))
      (node (ref "IC3") (pin "6") (pinfunction "INH_6") (pintype "input"))
      (node (ref "IC3") (pin "7") (pinfunction "VEE_7") (pintype "power_in"))
      (node (ref "IC3") (pin "8") (pinfunction "GND_8") (pintype "power_in"))
      (node (ref "IC7") (pin "2") (pinfunction "GND_2") (pintype "passive"))
      (node (ref "IC9") (pin "11") (pinfunction "V-_11") (pintype "power_in"))
      (node (ref "IC9") (pin "12") (pinfunction "+IN_12") (pintype "input"))
      (node (ref "J1") (pin "P1") (pinfunction "1_P1") (pintype "passive"))
      (node (ref "J1") (pin "P2") (pinfunction "2_P2") (pintype "passive"))
      (node (ref "J10") (pin "P1") (pinfunction "1_P1") (pintype "passive"))
      (node (ref "J11") (pin "P1") (pinfunction "1_P1") (pintype "passive"))
      (node (ref "J12") (pin "P1") (pinfunction "1_P1") (pintype "passive"))
      (node (ref "J2") (pin "P1") (pinfunction "1_P1") (pintype "passive"))
      (node (ref "J2") (pin "P2") (pinfunction "2_P2") (pintype "passive"))
      (node (ref "J3") (pin "P1") (pinfunction "1_P1") (pintype "passive"))
      (node (ref "J3") (pin "P2") (pinfunction "2_P2") (pintype "passive"))
      (node (ref "J4") (pin "P1") (pinfunction "1_P1") (pintype "passive"))
      (node (ref "J4") (pin "P2") (pinfunction "2_P2") (pintype "passive"))
      (node (ref "J5") (pin "P1") (pinfunction "1_P1") (pintype "passive"))
      (node (ref "J5") (pin "P2") (pinfunction "2_P2") (pintype "passive"))
      (node (ref "J6") (pin "P1") (pinfunction "1_P1") (pintype "passive"))
      (node (ref "J6") (pin "P2") (pinfunction "2_P2") (pintype "passive"))
      (node (ref "J7") (pin "P1") (pinfunction "1_P1") (pintype "passive"))
      (node (ref "J8") (pin "P1") (pinfunction "1_P1") (pintype "passive"))
      (node (ref "J9") (pin "P1") (pinfunction "1_P1") (pintype "passive"))
      (node (ref "JP6") (pin "1") (pinfunction "1_1") (pintype "passive"))
      (node (ref "JP8") (pin "3") (pinfunction "3_3") (pintype "passive"))
      (node (ref "JP8") (pin "4") (pinfunction "4_4") (pintype "passive"))
      (node (ref "JP8") (pin "5") (pinfunction "5_5") (pintype "passive"))
      (node (ref "JP8") (pin "6") (pinfunction "6_6") (pintype "passive"))
      (node (ref "JP8") (pin "7") (pinfunction "7_7") (pintype "passive"))
      (node (ref "JP8") (pin "8") (pinfunction "8_8") (pintype "passive"))
      (node (ref "POT_A") (pin "P$3") (pinfunction "A_P$3") (pintype "passive"))
      (node (ref "POT_B") (pin "P$3") (pinfunction "A_P$3") (pintype "passive"))
      (node (ref "POT_C") (pin "P$3") (pinfunction "A_P$3") (pintype "passive"))
      (node (ref "Q2") (pin "2") (pinfunction "LID1_2") (pintype "power_in"))
      (node (ref "Q2") (pin "4") (pinfunction "LID2_4") (pintype "power_in"))
      (node (ref "Q5") (pin "E") (pinfunction "E_E") (pintype "passive"))
      (node (ref "Q6") (pin "E") (pinfunction "E_E") (pintype "passive"))
      (node (ref "Q7") (pin "E") (pinfunction "E_E") (pintype "passive"))
      (node (ref "R13") (pin "2") (pinfunction "2_2") (pintype "passive"))
      (node (ref "R17") (pin "2") (pinfunction "2_2") (pintype "passive"))
      (node (ref "R50") (pin "2") (pinfunction "2_2") (pintype "passive"))
      (node (ref "R69") (pin "1") (pinfunction "1_1") (pintype "passive"))
      (node (ref "R70") (pin "1") (pinfunction "1_1") (pintype "passive"))
      (node (ref "R71") (pin "1") (pinfunction "1_1") (pintype "passive"))
      (node (ref "R9") (pin "2") (pinfunction "2_2") (pintype "passive"))
      (node (ref "SLD_A") (pin "1") (pinfunction "A_1") (pintype "passive"))
      (node (ref "SLD_B") (pin "1") (pinfunction "A_1") (pintype "passive"))
      (node (ref "SLD_C") (pin "1") (pinfunction "A_1") (pintype "passive"))
      (node (ref "SW_A") (pin "1") (pinfunction "1_1") (pintype "passive"))
      (node (ref "SW_A") (pin "2") (pinfunction "2_2") (pintype "passive"))
      (node (ref "SW_B") (pin "1") (pinfunction "1_1") (pintype "passive"))
      (node (ref "SW_B") (pin "2") (pinfunction "2_2") (pintype "passive"))
      (node (ref "SW_C") (pin "1") (pinfunction "1_1") (pintype "passive"))
      (node (ref "SW_C") (pin "2") (pinfunction "2_2") (pintype "passive"))
      (node (ref "U1") (pin "16") (pinfunction "VSS_2_16") (pintype "power_in"))
      (node (ref "U1") (pin "31") (pinfunction "BOOT0_31") (pintype "input"))
      (node (ref "U1") (pin "32") (pinfunction "VSS_1_32") (pintype "power_in"))
      (node (ref "U2") (pin "10") (pinfunction "+IN_10") (pintype "input"))
      (node (ref "U2") (pin "11") (pinfunction "V-_11") (pintype "power_in"))
      (node (ref "U2") (pin "12") (pinfunction "+IN_12") (pintype "input"))
      (node (ref "U2") (pin "3") (pinfunction "+IN_3") (pintype "input"))
      (node (ref "U2") (pin "5") (pinfunction "+IN_5") (pintype "input"))
      (node (ref "U4") (pin "10") (pinfunction "+IN_10") (pintype "input"))
      (node (ref "U4") (pin "12") (pinfunction "+IN_12") (pintype "input"))
      (node (ref "U4") (pin "3") (pinfunction "+IN_3") (pintype "input"))
      (node (ref "U4") (pin "5") (pinfunction "+IN_5") (pintype "input"))
    )
    (net (code "31") (name "LEDS_SCK") (class "Default")
      (node (ref "IC1") (pin "3") (pinfunction "SCLK_3") (pintype "bidirectional"))
      (node (ref "U1") (pin "26") (pinfunction "PB3_26") (pintype "bidirectional"))
    )
    (net (code "32") (name "LEDS_SIN") (class "Default")
      (node (ref "IC1") (pin "2") (pinfunction "SIN_2") (pintype "bidirectional"))
      (node (ref "U1") (pin "28") (pinfunction "PB5_28") (pintype "bidirectional"))
    )
    (net (code "33") (name "N_U") (class "Default")
      (node (ref "U2") (pin "6") (pinfunction "-IN_6") (pintype "input"))
      (node (ref "U2") (pin "7") (pinfunction "OUT_7") (pintype "output"))
    )
    (net (code "34") (name "Net-(C13-Pad1)") (class "Default")
      (node (ref "C13") (pin "1") (pinfunction "1_1") (pintype "passive"))
      (node (ref "D3") (pin "C") (pinfunction "C_C") (pintype "passive"))
      (node (ref "L3") (pin "1") (pinfunction "1_1") (pintype "passive"))
      (node (ref "L4") (pin "2") (pinfunction "2_2") (pintype "passive"))
      (node (ref "L5") (pin "2") (pinfunction "2_2") (pintype "passive"))
    )
    (net (code "35") (name "Net-(C34-Pad2)") (class "Default")
      (node (ref "C34") (pin "2") (pinfunction "2_2") (pintype "passive"))
      (node (ref "Q2") (pin "1") (pinfunction "1_1") (pintype "passive"))
      (node (ref "R22") (pin "2") (pinfunction "2_2") (pintype "passive"))
    )
    (net (code "36") (name "Net-(D1-PadC)") (class "Default")
      (node (ref "D1") (pin "C") (pinfunction "C_C") (pintype "passive"))
      (node (ref "Q7") (pin "B") (pinfunction "B_B") (pintype "passive"))
      (node (ref "R66") (pin "2") (pinfunction "2_2") (pintype "passive"))
      (node (ref "R69") (pin "2") (pinfunction "2_2") (pintype "passive"))
    )
    (net (code "37") (name "Net-(D2-PadC)") (class "Default")
      (node (ref "D2") (pin "C") (pinfunction "C_C") (pintype "passive"))
      (node (ref "Q5") (pin "B") (pinfunction "B_B") (pintype "passive"))
      (node (ref "R67") (pin "2") (pinfunction "2_2") (pintype "passive"))
      (node (ref "R70") (pin "2") (pinfunction "2_2") (pintype "passive"))
    )
    (net (code "38") (name "Net-(D4-PadA)") (class "Default")
      (node (ref "D4") (pin "A") (pinfunction "A_A") (pintype "passive"))
      (node (ref "L1") (pin "2") (pinfunction "2_2") (pintype "passive"))
    )
    (net (code "39") (name "Net-(D5-PadC)") (class "Default")
      (node (ref "D5") (pin "C") (pinfunction "C_C") (pintype "passive"))
      (node (ref "Q6") (pin "B") (pinfunction "B_B") (pintype "passive"))
      (node (ref "R68") (pin "2") (pinfunction "2_2") (pintype "passive"))
      (node (ref "R71") (pin "2") (pinfunction "2_2") (pintype "passive"))
    )
    (net (code "40") (name "Net-(IC1-IREF)") (class "Default")
      (node (ref "IC1") (pin "23") (pinfunction "IREF_23") (pintype "bidirectional"))
      (node (ref "R50") (pin "1") (pinfunction "1_1") (pintype "passive"))
    )
    (net (code "41") (name "Net-(IC1-OUT1)") (class "Default")
      (node (ref "IC1") (pin "6") (pinfunction "OUT1_6") (pintype "bidirectional"))
      (node (ref "R31") (pin "2") (pinfunction "2_2") (pintype "passive"))
    )
    (net (code "42") (name "Net-(IC1-OUT2)") (class "Default")
      (node (ref "IC1") (pin "7") (pinfunction "OUT2_7") (pintype "bidirectional"))
      (node (ref "MODE_C") (pin "RED_C") (pinfunction "RED_RED_C") (pintype "bidirectional"))
    )
    (net (code "43") (name "Net-(IC1-OUT3)") (class "Default")
      (node (ref "IC1") (pin "8") (pinfunction "OUT3_8") (pintype "bidirectional"))
      (node (ref "MODE_C") (pin "GREEN_C") (pinfunction "GRN_GREEN_C") (pintype "bidirectional"))
    )
    (net (code "44") (name "Net-(IC1-OUT4)") (class "Default")
      (node (ref "IC1") (pin "9") (pinfunction "OUT4_9") (pintype "bidirectional"))
      (node (ref "MODE_A") (pin "GREEN_C") (pinfunction "GRN_GREEN_C") (pintype "bidirectional"))
    )
    (net (code "45") (name "Net-(IC1-OUT5)") (class "Default")
      (node (ref "IC1") (pin "10") (pinfunction "OUT5_10") (pintype "bidirectional"))
      (node (ref "MODE_A") (pin "RED_C") (pinfunction "RED_RED_C") (pintype "bidirectional"))
    )
    (net (code "46") (name "Net-(IC1-OUT6)") (class "Default")
      (node (ref "IC1") (pin "11") (pinfunction "OUT6_11") (pintype "bidirectional"))
      (node (ref "MODE_B") (pin "GREEN_C") (pinfunction "GRN_GREEN_C") (pintype "bidirectional"))
    )
    (net (code "47") (name "Net-(IC1-OUT7)") (class "Default")
      (node (ref "IC1") (pin "12") (pinfunction "OUT7_12") (pintype "bidirectional"))
      (node (ref "MODE_B") (pin "RED_C") (pinfunction "RED_RED_C") (pintype "bidirectional"))
    )
    (net (code "48") (name "Net-(IC1-OUT8)") (class "Default")
      (node (ref "IC1") (pin "13") (pinfunction "OUT8_13") (pintype "bidirectional"))
      (node (ref "LED10") (pin "GREEN_C") (pinfunction "GRN_GREEN_C") (pintype "bidirectional"))
    )
    (net (code "49") (name "Net-(IC1-OUT9)") (class "Default")
      (node (ref "IC1") (pin "14") (pinfunction "OUT9_14") (pintype "bidirectional"))
      (node (ref "LED10") (pin "RED_C") (pinfunction "RED_RED_C") (pintype "bidirectional"))
    )
    (net (code "50") (name "Net-(IC1-OUT10)") (class "Default")
      (node (ref "IC1") (pin "15") (pinfunction "OUT10_15") (pintype "bidirectional"))
      (node (ref "LED11") (pin "RED_C") (pinfunction "RED_RED_C") (pintype "bidirectional"))
    )
    (net (code "51") (name "Net-(IC1-OUT11)") (class "Default")
      (node (ref "IC1") (pin "16") (pinfunction "OUT11_16") (pintype "bidirectional"))
      (node (ref "LED11") (pin "GREEN_C") (pinfunction "GRN_GREEN_C") (pintype "bidirectional"))
    )
    (net (code "52") (name "Net-(IC1-OUT12)") (class "Default")
      (node (ref "IC1") (pin "17") (pinfunction "OUT12_17") (pintype "bidirectional"))
      (node (ref "LED12") (pin "RED_C") (pinfunction "RED_RED_C") (pintype "bidirectional"))
    )
    (net (code "53") (name "Net-(IC1-OUT13)") (class "Default")
      (node (ref "IC1") (pin "18") (pinfunction "OUT13_18") (pintype "bidirectional"))
      (node (ref "LED12") (pin "GREEN_C") (pinfunction "GRN_GREEN_C") (pintype "bidirectional"))
    )
    (net (code "54") (name "Net-(IC1-OUT14)") (class "Default")
      (node (ref "IC1") (pin "19") (pinfunction "OUT14_19") (pintype "bidirectional"))
      (node (ref "R19") (pin "2") (pinfunction "2_2") (pintype "passive"))
    )
    (net (code "55") (name "Net-(IC1-OUT15)") (class "Default")
      (node (ref "IC1") (pin "20") (pinfunction "OUT15_20") (pintype "bidirectional"))
      (node (ref "R30") (pin "2") (pinfunction "2_2") (pintype "passive"))
    )
    (net (code "56") (name "Net-(IC1-VCC)") (class "Default")
      (node (ref "C7") (pin "1") (pinfunction "1_1") (pintype "passive"))
      (node (ref "C8") (pin "1") (pinfunction "1_1") (pintype "passive"))
      (node (ref "IC1") (pin "24") (pinfunction "VCC_24") (pintype "bidirectional"))
      (node (ref "L2") (pin "1") (pinfunction "1_1") (pintype "passive"))
    )
    (net (code "57") (name "Net-(IC2-VI)") (class "Default")
      (node (ref "C15") (pin "1") (pinfunction "1_1") (pintype "passive"))
      (node (ref "IC2") (pin "1") (pinfunction "VI_1") (pintype "input"))
      (node (ref "L3") (pin "2") (pinfunction "2_2") (pintype "passive"))
    )
    (net (code "58") (name "Net-(IC3A-X0)") (class "Default")
      (node (ref "IC3") (pin "13") (pinfunction "X0_13") (pintype "bidirectional"))
      (node (ref "POT_C") (pin "P$2") (pinfunction "S_P$2") (pintype "passive"))
    )
    (net (code "59") (name "Net-(IC3A-X1)") (class "Default")
      (node (ref "IC3") (pin "14") (pinfunction "X1_14") (pintype "bidirectional"))
      (node (ref "SLD_C") (pin "2") (pinfunction "S_2") (pintype "passive"))
    )
    (net (code "60") (name "Net-(IC3A-X2)") (class "Default")
      (node (ref "IC3") (pin "15") (pinfunction "X2_15") (pintype "bidirectional"))
      (node (ref "SLD_B") (pin "2") (pinfunction "S_2") (pintype "passive"))
    )
    (net (code "61") (name "Net-(IC3A-X3)") (class "Default")
      (node (ref "IC3") (pin "12") (pinfunction "X3_12") (pintype "bidirectional"))
      (node (ref "POT_A") (pin "P$2") (pinfunction "S_P$2") (pintype "passive"))
    )
    (net (code "62") (name "Net-(IC3A-X4)") (class "Default")
      (node (ref "IC3") (pin "1") (pinfunction "X4_1") (pintype "bidirectional"))
      (node (ref "SLD_A") (pin "2") (pinfunction "S_2") (pintype "passive"))
    )
    (net (code "63") (name "Net-(IC3A-X6)") (class "Default")
      (node (ref "IC3") (pin "2") (pinfunction "X6_2") (pintype "bidirectional"))
      (node (ref "POT_B") (pin "P$2") (pinfunction "S_P$2") (pintype "passive"))
    )
    (net (code "64") (name "Net-(IC7-VI)") (class "Default")
      (node (ref "C20") (pin "1") (pinfunction "1_1") (pintype "passive"))
      (node (ref "IC7") (pin "3") (pinfunction "VI_3") (pintype "input"))
      (node (ref "L4") (pin "1") (pinfunction "1_1") (pintype "passive"))
    )
    (net (code "65") (name "Net-(IC9A-+IN)") (class "Default")
      (node (ref "IC9") (pin "3") (pinfunction "+IN_3") (pintype "input"))
      (node (ref "R8") (pin "2") (pinfunction "2_2") (pintype "passive"))
      (node (ref "R9") (pin "1") (pinfunction "1_1") (pintype "passive"))
    )
    (net (code "66") (name "Net-(IC9A--IN)") (class "Default")
      (node (ref "IC9") (pin "2") (pinfunction "-IN_2") (pintype "input"))
      (node (ref "R10") (pin "1") (pinfunction "1_1") (pintype "passive"))
    )
    (net (code "67") (name "Net-(IC9A-OUT)") (class "Default")
      (node (ref "IC9") (pin "1") (pinfunction "OUT_1") (pintype "output"))
      (node (ref "R7") (pin "2") (pinfunction "2_2") (pintype "passive"))
      (node (ref "R8") (pin "1") (pinfunction "1_1") (pintype "passive"))
    )
    (net (code "68") (name "Net-(IC9B-+IN)") (class "Default")
      (node (ref "IC9") (pin "5") (pinfunction "+IN_5") (pintype "input"))
      (node (ref "R12") (pin "2") (pinfunction "2_2") (pintype "passive"))
      (node (ref "R13") (pin "1") (pinfunction "1_1") (pintype "passive"))
    )
    (net (code "69") (name "Net-(IC9B--IN)") (class "Default")
      (node (ref "IC9") (pin "6") (pinfunction "-IN_6") (pintype "input"))
      (node (ref "R14") (pin "1") (pinfunction "1_1") (pintype "passive"))
    )
    (net (code "70") (name "Net-(IC9B-OUT)") (class "Default")
      (node (ref "IC9") (pin "7") (pinfunction "OUT_7") (pintype "output"))
      (node (ref "R11") (pin "2") (pinfunction "2_2") (pintype "passive"))
      (node (ref "R12") (pin "1") (pinfunction "1_1") (pintype "passive"))
    )
    (net (code "71") (name "Net-(IC9C-+IN)") (class "Default")
      (node (ref "IC9") (pin "10") (pinfunction "+IN_10") (pintype "input"))
      (node (ref "R16") (pin "2") (pinfunction "2_2") (pintype "passive"))
      (node (ref "R17") (pin "1") (pinfunction "1_1") (pintype "passive"))
    )
    (net (code "72") (name "Net-(IC9C--IN)") (class "Default")
      (node (ref "IC9") (pin "9") (pinfunction "-IN_9") (pintype "input"))
      (node (ref "R20") (pin "1") (pinfunction "1_1") (pintype "passive"))
    )
    (net (code "73") (name "Net-(IC9C-OUT)") (class "Default")
      (node (ref "IC9") (pin "8") (pinfunction "OUT_8") (pintype "output"))
      (node (ref "R15") (pin "2") (pinfunction "2_2") (pintype "passive"))
      (node (ref "R16") (pin "1") (pinfunction "1_1") (pintype "passive"))
    )
    (net (code "74") (name "Net-(IC9D--IN)") (class "Default")
      (node (ref "IC9") (pin "13") (pinfunction "-IN_13") (pintype "input"))
      (node (ref "IC9") (pin "14") (pinfunction "OUT_14") (pintype "output"))
    )
    (net (code "75") (name "Net-(J10-3)") (class "Default")
      (node (ref "J10") (pin "P3") (pinfunction "3_P3") (pintype "passive"))
      (node (ref "R11") (pin "1") (pinfunction "1_1") (pintype "passive"))
    )
    (net (code "76") (name "Net-(Q2B-2)") (class "Default")
      (node (ref "C35") (pin "2") (pinfunction "2_2") (pintype "passive"))
      (node (ref "Q2") (pin "3") (pinfunction "2_3") (pintype "passive"))
      (node (ref "R21") (pin "2") (pinfunction "2_2") (pintype "passive"))
    )
    (net (code "77") (name "Net-(SLD_AA-C)") (class "Default")
      (node (ref "R19") (pin "1") (pinfunction "1_1") (pintype "passive"))
      (node (ref "SLD_A") (pin "E") (pinfunction "C_E") (pintype "passive"))
    )
    (net (code "78") (name "Net-(SLD_BA-C)") (class "Default")
      (node (ref "R30") (pin "1") (pinfunction "1_1") (pintype "passive"))
      (node (ref "SLD_B") (pin "E") (pinfunction "C_E") (pintype "passive"))
    )
    (net (code "79") (name "Net-(SLD_CA-C)") (class "Default")
      (node (ref "R31") (pin "1") (pinfunction "1_1") (pintype "passive"))
      (node (ref "SLD_C") (pin "E") (pinfunction "C_E") (pintype "passive"))
    )
    (net (code "80") (name "Net-(U1-PF0{slash}OSC_IN)") (class "Default")
      (node (ref "R21") (pin "1") (pinfunction "1_1") (pintype "passive"))
      (node (ref "U1") (pin "2") (pinfunction "PF0/OSC_IN_2") (pintype "bidirectional"))
    )
    (net (code "81") (name "Net-(U1-PF1{slash}OSC_OUT)") (class "Default")
      (node (ref "R22") (pin "1") (pinfunction "1_1") (pintype "passive"))
      (node (ref "U1") (pin "3") (pinfunction "PF1/OSC_OUT_3") (pintype "bidirectional"))
    )
    (net (code "82") (name "Net-(U2A--IN)") (class "Default")
      (node (ref "C12") (pin "1") (pinfunction "1_1") (pintype "passive"))
      (node (ref "R29") (pin "1") (pinfunction "1_1") (pintype "passive"))
      (node (ref "R4") (pin "1") (pinfunction "1_1") (pintype "passive"))
      (node (ref "R5") (pin "2") (pinfunction "2_2") (pintype "passive"))
      (node (ref "U2") (pin "2") (pinfunction "-IN_2") (pintype "input"))
    )
    (net (code "83") (name "Net-(U2C--IN)") (class "Default")
      (node (ref "C26") (pin "1") (pinfunction "1_1") (pintype "passive"))
      (node (ref "R26") (pin "2") (pinfunction "2_2") (pintype "passive"))
      (node (ref "R28") (pin "1") (pinfunction "1_1") (pintype "passive"))
      (node (ref "R6") (pin "1") (pinfunction "1_1") (pintype "passive"))
      (node (ref "U2") (pin "9") (pinfunction "-IN_9") (pintype "input"))
    )
    (net (code "84") (name "Net-(U2D--IN)") (class "Default")
      (node (ref "C28") (pin "1") (pinfunction "1_1") (pintype "passive"))
      (node (ref "R51") (pin "1") (pinfunction "1_1") (pintype "passive"))
      (node (ref "R52") (pin "2") (pinfunction "2_2") (pintype "passive"))
      (node (ref "R53") (pin "1") (pinfunction "1_1") (pintype "passive"))
      (node (ref "U2") (pin "13") (pinfunction "-IN_13") (pintype "input"))
    )
    (net (code "85") (name "Net-(U4A--IN)") (class "Default")
      (node (ref "C1") (pin "1") (pinfunction "1_1") (pintype "passive"))
      (node (ref "R2") (pin "1") (pinfunction "1_1") (pintype "passive"))
      (node (ref "R41") (pin "2") (pinfunction "2_2") (pintype "passive"))
      (node (ref "R47") (pin "1") (pinfunction "1_1") (pintype "passive"))
      (node (ref "U4") (pin "2") (pinfunction "-IN_2") (pintype "input"))
    )
    (net (code "86") (name "Net-(U4A-OUT)") (class "Default")
      (node (ref "C1") (pin "2") (pinfunction "2_2") (pintype "passive"))
      (node (ref "R35") (pin "2") (pinfunction "2_2") (pintype "passive"))
      (node (ref "U4") (pin "1") (pinfunction "OUT_1") (pintype "output"))
    )
    (net (code "87") (name "Net-(U4B--IN)") (class "Default")
      (node (ref "C2") (pin "1") (pinfunction "1_1") (pintype "passive"))
      (node (ref "R23") (pin "2") (pinfunction "2_2") (pintype "passive"))
      (node (ref "R24") (pin "1") (pinfunction "1_1") (pintype "passive"))
      (node (ref "R25") (pin "1") (pinfunction "1_1") (pintype "passive"))
      (node (ref "U4") (pin "6") (pinfunction "-IN_6") (pintype "input"))
    )
    (net (code "88") (name "Net-(U4B-OUT)") (class "Default")
      (node (ref "C2") (pin "2") (pinfunction "2_2") (pintype "passive"))
      (node (ref "R3") (pin "2") (pinfunction "2_2") (pintype "passive"))
      (node (ref "U4") (pin "7") (pinfunction "OUT_7") (pintype "output"))
    )
    (net (code "89") (name "Net-(U4C--IN)") (class "Default")
      (node (ref "C3") (pin "1") (pinfunction "1_1") (pintype "passive"))
      (node (ref "R32") (pin "2") (pinfunction "2_2") (pintype "passive"))
      (node (ref "R33") (pin "1") (pinfunction "1_1") (pintype "passive"))
      (node (ref "R34") (pin "1") (pinfunction "1_1") (pintype "passive"))
      (node (ref "U4") (pin "9") (pinfunction "-IN_9") (pintype "input"))
    )
    (net (code "90") (name "Net-(U4C-OUT)") (class "Default")
      (node (ref "C3") (pin "2") (pinfunction "2_2") (pintype "passive"))
      (node (ref "R27") (pin "2") (pinfunction "2_2") (pintype "passive"))
      (node (ref "U4") (pin "8") (pinfunction "OUT_8") (pintype "output"))
    )
    (net (code "91") (name "Net-(U4D--IN)") (class "Default")
      (node (ref "U4") (pin "13") (pinfunction "-IN_13") (pintype "input"))
      (node (ref "U4") (pin "14") (pinfunction "OUT_14") (pintype "output"))
    )
    (net (code "92") (name "POTS_ADDR_A") (class "Default")
      (node (ref "IC3") (pin "11") (pinfunction "A_11") (pintype "input"))
      (node (ref "U1") (pin "13") (pinfunction "PA7_13") (pintype "bidirectional"))
    )
    (net (code "93") (name "POTS_ADDR_B") (class "Default")
      (node (ref "IC3") (pin "10") (pinfunction "B_10") (pintype "input"))
      (node (ref "U1") (pin "18") (pinfunction "PA8_18") (pintype "bidirectional"))
    )
    (net (code "94") (name "POTS_ADDR_C") (class "Default")
      (node (ref "IC3") (pin "9") (pinfunction "C_9") (pintype "input"))
      (node (ref "U1") (pin "19") (pinfunction "PA9_19") (pintype "bidirectional"))
    )
    (net (code "95") (name "RESET") (class "Default")
      (node (ref "C36") (pin "1") (pinfunction "1_1") (pintype "passive"))
      (node (ref "JP6") (pin "4") (pinfunction "4_4") (pintype "passive"))
      (node (ref "R18") (pin "2") (pinfunction "2_2") (pintype "passive"))
      (node (ref "U1") (pin "4") (pinfunction "NRST_4") (pintype "bidirectional"))
    )
    (net (code "96") (name "SWCLK") (class "Default")
      (node (ref "JP6") (pin "3") (pinfunction "3_3") (pintype "passive"))
      (node (ref "U1") (pin "24") (pinfunction "PA14_24") (pintype "bidirectional"))
    )
    (net (code "97") (name "SWDIO") (class "Default")
      (node (ref "JP6") (pin "2") (pinfunction "2_2") (pintype "passive"))
      (node (ref "U1") (pin "23") (pinfunction "PA13_23") (pintype "bidirectional"))
    )
    (net (code "98") (name "SW_MODE_A") (class "Default")
      (node (ref "SW_A") (pin "3") (pinfunction "3_3") (pintype "passive"))
      (node (ref "SW_A") (pin "4") (pinfunction "4_4") (pintype "passive"))
      (node (ref "U1") (pin "27") (pinfunction "PB4_27") (pintype "bidirectional"))
    )
    (net (code "99") (name "SW_MODE_B") (class "Default")
      (node (ref "SW_B") (pin "3") (pinfunction "3_3") (pintype "passive"))
      (node (ref "SW_B") (pin "4") (pinfunction "4_4") (pintype "passive"))
      (node (ref "U1") (pin "29") (pinfunction "PB6_29") (pintype "bidirectional"))
    )
    (net (code "100") (name "SW_MODE_C") (class "Default")
      (node (ref "SW_C") (pin "3") (pinfunction "3_3") (pintype "passive"))
      (node (ref "SW_C") (pin "4") (pinfunction "4_4") (pintype "passive"))
      (node (ref "U1") (pin "30") (pinfunction "PB7_30") (pintype "bidirectional"))
    )
    (net (code "101") (name "VCC") (class "Default")
      (node (ref "C14") (pin "1") (pinfunction "1_1") (pintype "passive"))
      (node (ref "C21") (pin "1") (pinfunction "1_1") (pintype "passive"))
      (node (ref "C4") (pin "1") (pinfunction "1_1") (pintype "passive"))
      (node (ref "C50") (pin "1") (pinfunction "1_1") (pintype "passive"))
      (node (ref "IC9") (pin "4") (pinfunction "V+_4") (pintype "power_in"))
      (node (ref "L5") (pin "1") (pinfunction "1_1") (pintype "passive"))
      (node (ref "U4") (pin "4") (pinfunction "V+_4") (pintype "power_in"))
    )
    (net (code "102") (name "VEE") (class "Default")
      (node (ref "C16") (pin "2") (pinfunction "2_2") (pintype "passive"))
      (node (ref "C18") (pin "2") (pinfunction "2_2") (pintype "passive"))
      (node (ref "C23") (pin "2") (pinfunction "2_2") (pintype "passive"))
      (node (ref "L1") (pin "1") (pinfunction "1_1") (pintype "passive"))
      (node (ref "R1") (pin "1") (pinfunction "1_1") (pintype "passive"))
      (node (ref "U4") (pin "11") (pinfunction "V-_11") (pintype "power_in"))
    )
    (net (code "103") (name "unconnected-(IC1-LAT-Pad4)") (class "Default")
      (node (ref "IC1") (pin "4") (pinfunction "LAT_4") (pintype "bidirectional"))
    )
    (net (code "104") (name "unconnected-(IC1-OUT0-Pad5)") (class "Default")
      (node (ref "IC1") (pin "5") (pinfunction "OUT0_5") (pintype "bidirectional"))
    )
    (net (code "105") (name "unconnected-(IC1-SOUT-Pad22)") (class "Default")
      (node (ref "IC1") (pin "22") (pinfunction "SOUT_22") (pintype "bidirectional"))
    )
    (net (code "106") (name "unconnected-(IC3A-X5-Pad5)") (class "Default")
      (node (ref "IC3") (pin "5") (pinfunction "X5_5") (pintype "bidirectional"))
    )
    (net (code "107") (name "unconnected-(IC3A-X7-Pad4)") (class "Default")
      (node (ref "IC3") (pin "4") (pinfunction "X7_4") (pintype "bidirectional"))
    )
    (net (code "108") (name "unconnected-(J7-2-PadP2)") (class "Default")
      (node (ref "J7") (pin "P2") (pinfunction "2_P2") (pintype "passive"))
    )
    (net (code "109") (name "unconnected-(J8-2-PadP2)") (class "Default")
      (node (ref "J8") (pin "P2") (pinfunction "2_P2") (pintype "passive"))
    )
    (net (code "110") (name "unconnected-(J9-2-PadP2)") (class "Default")
      (node (ref "J9") (pin "P2") (pinfunction "2_P2") (pintype "passive"))
    )
    (net (code "111") (name "unconnected-(J10-2-PadP2)") (class "Default")
      (node (ref "J10") (pin "P2") (pinfunction "2_P2") (pintype "passive"))
    )
    (net (code "112") (name "unconnected-(J11-2-PadP2)") (class "Default")
      (node (ref "J11") (pin "P2") (pinfunction "2_P2") (pintype "passive"))
    )
    (net (code "113") (name "unconnected-(J12-2-PadP2)") (class "Default")
      (node (ref "J12") (pin "P2") (pinfunction "2_P2") (pintype "passive"))
    )
  )
)
